# Airquality.net
KiCad netlist of a schematic drawn in EAGLE
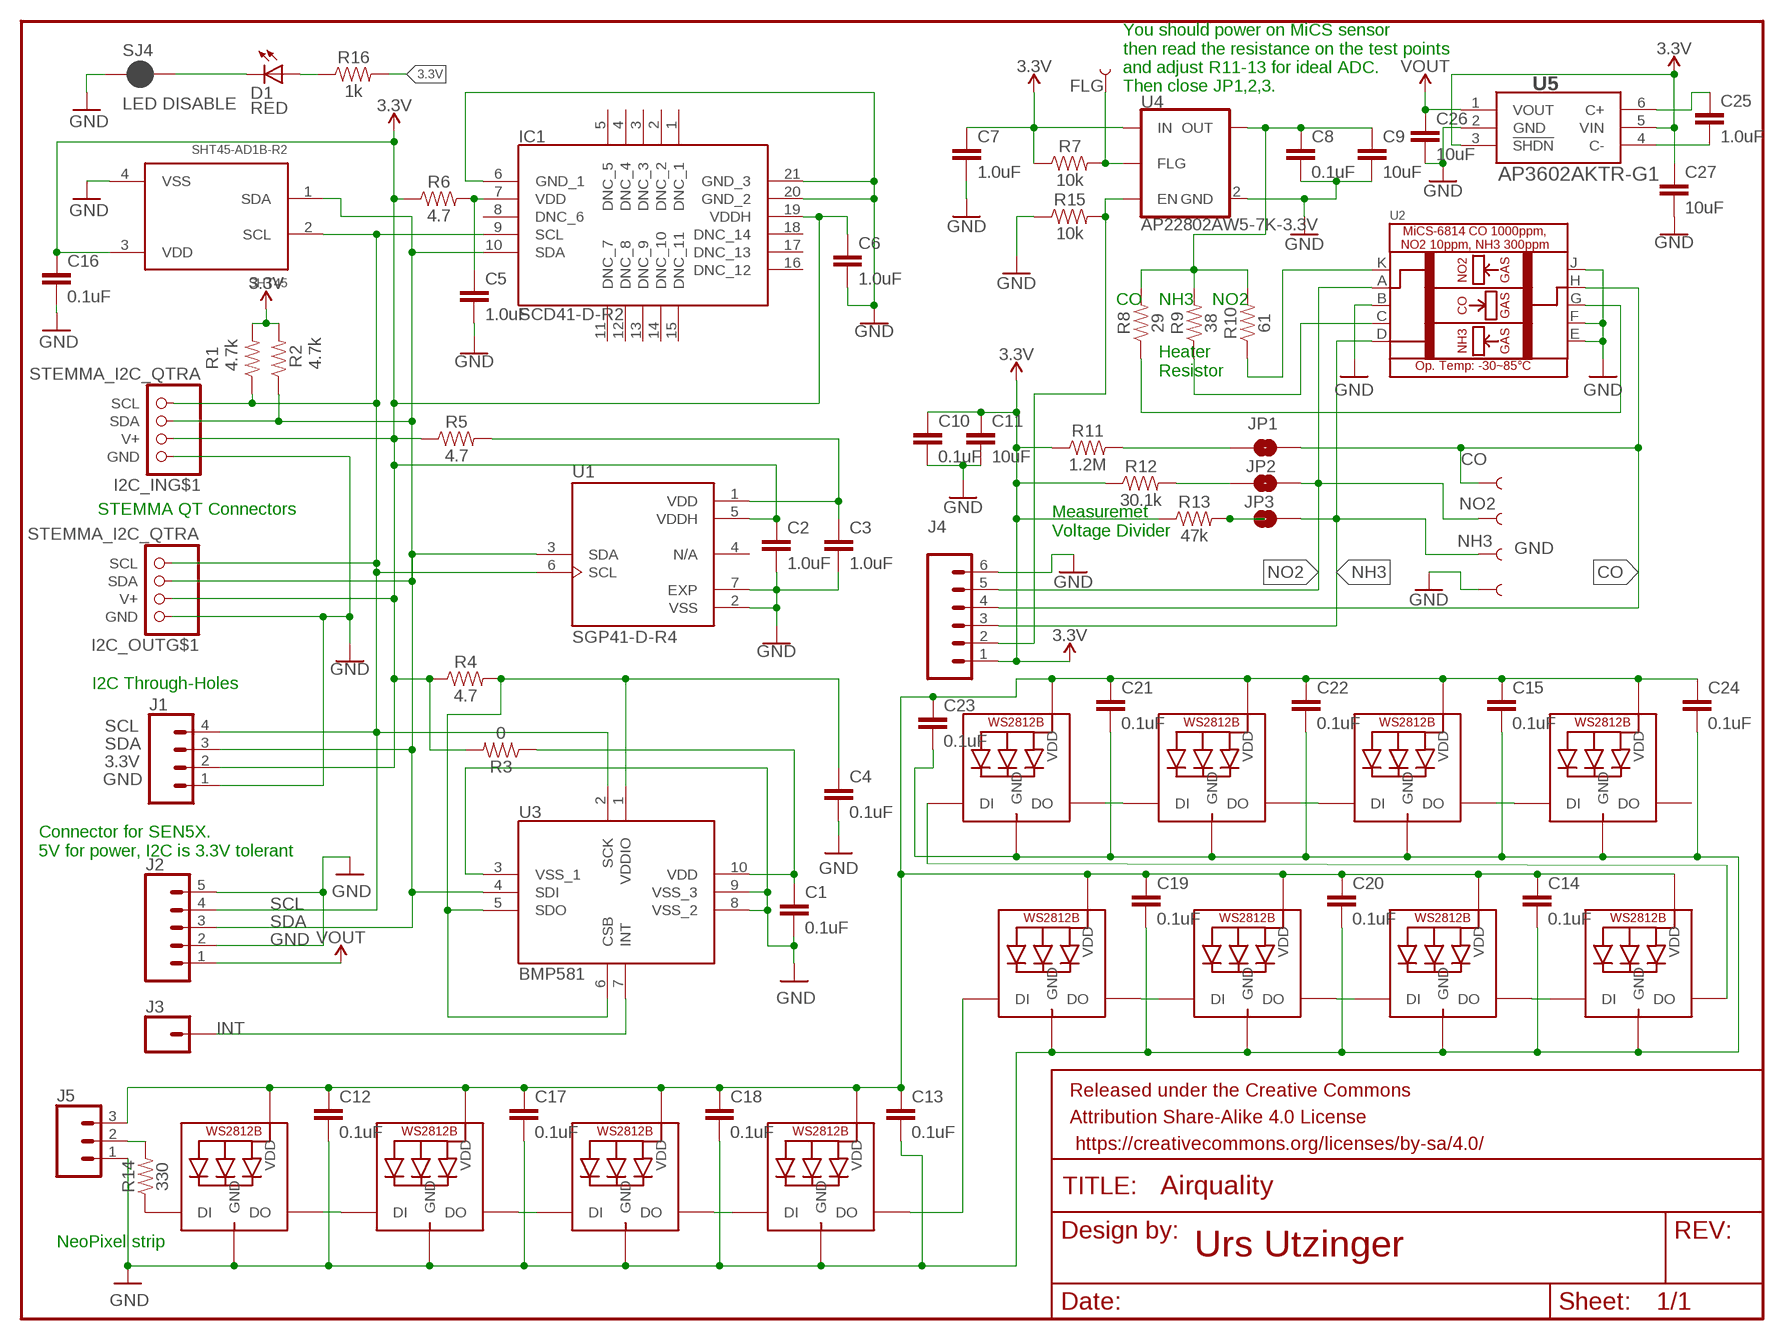
[diagram p0: schematic, sheet 1]

(export (version "E")
  (design (tool "Eeschema 10.0.6"))
  (components
    (comp (ref "C1")
      (value "0.1uF")
      (footprint "eagle-import:0603")
      (libsource (lib "eagle-import") (part "0.1UF-0603-25V-(+80/-20%)"))
    )
    (comp (ref "C2")
      (value "1.0uF")
      (footprint "eagle-import:0603")
      (libsource (lib "eagle-import") (part "1.0UF-0603-16V-10%"))
    )
    (comp (ref "C3")
      (value "1.0uF")
      (footprint "eagle-import:0603")
      (libsource (lib "eagle-import") (part "1.0UF-0603-16V-10%"))
    )
    (comp (ref "C4")
      (value "0.1uF")
      (footprint "eagle-import:0603")
      (libsource (lib "eagle-import") (part "0.1UF-0603-25V-(+80/-20%)"))
    )
    (comp (ref "C5")
      (value "1.0uF")
      (footprint "eagle-import:0603")
      (libsource (lib "eagle-import") (part "1.0UF-0603-16V-10%"))
    )
    (comp (ref "C6")
      (value "1.0uF")
      (footprint "eagle-import:0603")
      (libsource (lib "eagle-import") (part "1.0UF-0603-16V-10%"))
    )
    (comp (ref "C7")
      (value "1.0uF")
      (footprint "eagle-import:0603")
      (libsource (lib "eagle-import") (part "1.0UF-0603-16V-10%"))
    )
    (comp (ref "C8")
      (value "0.1uF")
      (footprint "eagle-import:0603")
      (libsource (lib "eagle-import") (part "0.1UF-0603-25V-(+80/-20%)"))
    )
    (comp (ref "C9")
      (value "10uF")
      (footprint "eagle-import:0603")
      (libsource (lib "eagle-import") (part "10UF-0603-6.3V-20%"))
    )
    (comp (ref "C10")
      (value "0.1uF")
      (footprint "eagle-import:0603")
      (libsource (lib "eagle-import") (part "0.1UF-0603-25V-(+80/-20%)"))
    )
    (comp (ref "C11")
      (value "10uF")
      (footprint "eagle-import:0603")
      (libsource (lib "eagle-import") (part "10UF-0603-6.3V-20%"))
    )
    (comp (ref "C12")
      (value "0.1uF")
      (footprint "eagle-import:0402")
      (libsource (lib "eagle-import") (part "0.1UF-0402-16V-10%"))
    )
    (comp (ref "C13")
      (value "0.1uF")
      (footprint "eagle-import:0402")
      (libsource (lib "eagle-import") (part "0.1UF-0402-16V-10%"))
    )
    (comp (ref "C14")
      (value "0.1uF")
      (footprint "eagle-import:0402")
      (libsource (lib "eagle-import") (part "0.1UF-0402-16V-10%"))
    )
    (comp (ref "C15")
      (value "0.1uF")
      (footprint "eagle-import:0402")
      (libsource (lib "eagle-import") (part "0.1UF-0402-16V-10%"))
    )
    (comp (ref "C16")
      (value "0.1uF")
      (footprint "eagle-import:0603")
      (libsource (lib "eagle-import") (part "0.1UF-0603-25V-(+80/-20%)"))
    )
    (comp (ref "C17")
      (value "0.1uF")
      (footprint "eagle-import:0402")
      (libsource (lib "eagle-import") (part "0.1UF-0402-16V-10%"))
    )
    (comp (ref "C18")
      (value "0.1uF")
      (footprint "eagle-import:0402")
      (libsource (lib "eagle-import") (part "0.1UF-0402-16V-10%"))
    )
    (comp (ref "C19")
      (value "0.1uF")
      (footprint "eagle-import:0402")
      (libsource (lib "eagle-import") (part "0.1UF-0402-16V-10%"))
    )
    (comp (ref "C20")
      (value "0.1uF")
      (footprint "eagle-import:0402")
      (libsource (lib "eagle-import") (part "0.1UF-0402-16V-10%"))
    )
    (comp (ref "C21")
      (value "0.1uF")
      (footprint "eagle-import:0402")
      (libsource (lib "eagle-import") (part "0.1UF-0402-16V-10%"))
    )
    (comp (ref "C22")
      (value "0.1uF")
      (footprint "eagle-import:0402")
      (libsource (lib "eagle-import") (part "0.1UF-0402-16V-10%"))
    )
    (comp (ref "C23")
      (value "0.1uF")
      (footprint "eagle-import:0402")
      (libsource (lib "eagle-import") (part "0.1UF-0402-16V-10%"))
    )
    (comp (ref "C24")
      (value "0.1uF")
      (footprint "eagle-import:0402")
      (libsource (lib "eagle-import") (part "0.1UF-0402-16V-10%"))
    )
    (comp (ref "C25")
      (value "1.0uF")
      (footprint "eagle-import:0402")
      (libsource (lib "eagle-import") (part "1.0UF-0402-16V-10%"))
    )
    (comp (ref "C26")
      (value "10uF")
      (footprint "eagle-import:0603")
      (libsource (lib "eagle-import") (part "10UF-0603-6.3V-20%"))
    )
    (comp (ref "C27")
      (value "10uF")
      (footprint "eagle-import:0603")
      (libsource (lib "eagle-import") (part "10UF-0603-6.3V-20%"))
    )
    (comp (ref "CO")
      (value "TEST-POINT3X4")
      (footprint "eagle-import:PAD.03X.04")
      (libsource (lib "eagle-import") (part "TEST-POINT3X4"))
    )
    (comp (ref "D1")
      (value "RED")
      (footprint "eagle-import:LED-0603")
      (libsource (lib "eagle-import") (part "LED-RED0603"))
    )
    (comp (ref "FLG")
      (value "TEST-POINT3X4")
      (footprint "eagle-import:PAD.03X.04")
      (libsource (lib "eagle-import") (part "TEST-POINT3X4"))
    )
    (comp (ref "FRAME1")
      (value "FRAME-LETTERNO_PACKAGE")
      (footprint "eagle-import:DUMMY")
      (fields (field (name "DESIGNER") "Nobody"))
      (libsource (lib "eagle-import") (part "FRAME-LETTERNO_PACKAGE"))
    )
    (comp (ref "GND")
      (value "TEST-POINT3X4")
      (footprint "eagle-import:PAD.03X.04")
      (libsource (lib "eagle-import") (part "TEST-POINT3X4"))
    )
    (comp (ref "I2C_IN")
      (value "STEMMA_I2C_QTRA")
      (footprint "eagle-import:JST_SH4_RA")
      (libsource (lib "eagle-import") (part "STEMMA_I2C_QTRA"))
    )
    (comp (ref "I2C_OUT")
      (value "STEMMA_I2C_QTRA")
      (footprint "eagle-import:JST_SH4_RA")
      (libsource (lib "eagle-import") (part "STEMMA_I2C_QTRA"))
    )
    (comp (ref "IC1")
      (value "SCD41-D-R2")
      (footprint "eagle-import:SCD41DR2")
      (fields (field (name "MOUSER_PART_NUMBER") "403-SCD41-D-R2"))
      (libsource (lib "eagle-import") (part "SCD41-D-R2"))
    )
    (comp (ref "J1")
      (value "CONN_04")
      (footprint "eagle-import:1X04")
      (libsource (lib "eagle-import") (part "CONN_04"))
    )
    (comp (ref "J2")
      (value "CONN_05")
      (footprint "eagle-import:1X05")
      (libsource (lib "eagle-import") (part "CONN_05"))
    )
    (comp (ref "J3")
      (value "CONN_01")
      (footprint "eagle-import:1X01")
      (libsource (lib "eagle-import") (part "CONN_01"))
    )
    (comp (ref "J4")
      (value "CONN_06SILK_FEMALE_PTH")
      (footprint "eagle-import:1X06")
      (libsource (lib "eagle-import") (part "CONN_06SILK_FEMALE_PTH"))
    )
    (comp (ref "J5")
      (value "CONN_03")
      (footprint "eagle-import:1X03")
      (libsource (lib "eagle-import") (part "CONN_03"))
    )
    (comp (ref "JP1")
      (value "JUMPER-SMT_2_NO_SILK")
      (footprint "eagle-import:SMT-JUMPER_2_NO_SILK")
      (libsource (lib "eagle-import") (part "JUMPER-SMT_2_NO_SILK"))
    )
    (comp (ref "JP2")
      (value "JUMPER-SMT_2_NO_SILK")
      (footprint "eagle-import:SMT-JUMPER_2_NO_SILK")
      (libsource (lib "eagle-import") (part "JUMPER-SMT_2_NO_SILK"))
    )
    (comp (ref "JP3")
      (value "JUMPER-SMT_2_NO_SILK")
      (footprint "eagle-import:SMT-JUMPER_2_NO_SILK")
      (libsource (lib "eagle-import") (part "JUMPER-SMT_2_NO_SILK"))
    )
    (comp (ref "LED0")
      (value "WS2812B_2020")
      (footprint "eagle-import:WS2812B_2020")
      (libsource (lib "eagle-import") (part "WS2812B_2020"))
    )
    (comp (ref "LED1")
      (value "WS2812B_2020")
      (footprint "eagle-import:WS2812B_2020")
      (libsource (lib "eagle-import") (part "WS2812B_2020"))
    )
    (comp (ref "LED2")
      (value "WS2812B_2020")
      (footprint "eagle-import:WS2812B_2020")
      (libsource (lib "eagle-import") (part "WS2812B_2020"))
    )
    (comp (ref "LED3")
      (value "WS2812B_2020")
      (footprint "eagle-import:WS2812B_2020")
      (libsource (lib "eagle-import") (part "WS2812B_2020"))
    )
    (comp (ref "LED4")
      (value "WS2812B_2020")
      (footprint "eagle-import:WS2812B_2020")
      (libsource (lib "eagle-import") (part "WS2812B_2020"))
    )
    (comp (ref "LED5")
      (value "WS2812B_2020")
      (footprint "eagle-import:WS2812B_2020")
      (libsource (lib "eagle-import") (part "WS2812B_2020"))
    )
    (comp (ref "LED6")
      (value "WS2812B_2020")
      (footprint "eagle-import:WS2812B_2020")
      (libsource (lib "eagle-import") (part "WS2812B_2020"))
    )
    (comp (ref "LED7")
      (value "WS2812B_2020")
      (footprint "eagle-import:WS2812B_2020")
      (libsource (lib "eagle-import") (part "WS2812B_2020"))
    )
    (comp (ref "LED8")
      (value "WS2812B_2020")
      (footprint "eagle-import:WS2812B_2020")
      (libsource (lib "eagle-import") (part "WS2812B_2020"))
    )
    (comp (ref "LED9")
      (value "WS2812B_2020")
      (footprint "eagle-import:WS2812B_2020")
      (libsource (lib "eagle-import") (part "WS2812B_2020"))
    )
    (comp (ref "LED10")
      (value "WS2812B_2020")
      (footprint "eagle-import:WS2812B_2020")
      (libsource (lib "eagle-import") (part "WS2812B_2020"))
    )
    (comp (ref "LED11")
      (value "WS2812B_2020")
      (footprint "eagle-import:WS2812B_2020")
      (libsource (lib "eagle-import") (part "WS2812B_2020"))
    )
    (comp (ref "NH3")
      (value "TEST-POINT3X4")
      (footprint "eagle-import:PAD.03X.04")
      (libsource (lib "eagle-import") (part "TEST-POINT3X4"))
    )
    (comp (ref "NO2")
      (value "TEST-POINT3X4")
      (footprint "eagle-import:PAD.03X.04")
      (libsource (lib "eagle-import") (part "TEST-POINT3X4"))
    )
    (comp (ref "R1")
      (value "4.7k")
      (footprint "eagle-import:0603")
      (libsource (lib "eagle-import") (part "4.7KOHM-0603-1/10W-1%"))
    )
    (comp (ref "R2")
      (value "4.7k")
      (footprint "eagle-import:0603")
      (libsource (lib "eagle-import") (part "4.7KOHM-0603-1/10W-1%"))
    )
    (comp (ref "R3")
      (value "0")
      (footprint "eagle-import:0603")
      (libsource (lib "eagle-import") (part "10OHM-0603-1/10W-5%"))
    )
    (comp (ref "R4")
      (value "4.7")
      (footprint "eagle-import:0603")
      (libsource (lib "eagle-import") (part "10OHM-0603-1/10W-5%"))
    )
    (comp (ref "R5")
      (value "4.7")
      (footprint "eagle-import:0603")
      (libsource (lib "eagle-import") (part "10OHM-0603-1/10W-1%"))
    )
    (comp (ref "R6")
      (value "4.7")
      (footprint "eagle-import:0603")
      (libsource (lib "eagle-import") (part "10OHM-0603-1/10W-1%"))
    )
    (comp (ref "R7")
      (value "10k")
      (footprint "eagle-import:0603")
      (libsource (lib "eagle-import") (part "10KOHM-0603-1/10W-1%"))
    )
    (comp (ref "R8")
      (value "29")
      (footprint "eagle-import:0603")
      (libsource (lib "eagle-import") (part "27OHM-0603-1/10W-1%"))
    )
    (comp (ref "R9")
      (value "38")
      (footprint "eagle-import:0603")
      (libsource (lib "eagle-import") (part "33OHM-0603-1/10W-1%"))
    )
    (comp (ref "R10")
      (value "61")
      (footprint "eagle-import:0603")
      (libsource (lib "eagle-import") (part "82OHM-0603-1/10W-1%"))
    )
    (comp (ref "R11")
      (value "1.2M")
      (footprint "eagle-import:0603")
      (libsource (lib "eagle-import") (part "1.2MOHM-0603-1/10W-1%"))
    )
    (comp (ref "R12")
      (value "30.1k")
      (footprint "eagle-import:0603")
      (libsource (lib "eagle-import") (part "30.1KOHM-0603-1/10W-1%"))
    )
    (comp (ref "R13")
      (value "47k")
      (footprint "eagle-import:0603")
      (libsource (lib "eagle-import") (part "47KOHM-0603-1/10W-1%"))
    )
    (comp (ref "R14")
      (value "330")
      (footprint "eagle-import:0603")
      (libsource (lib "eagle-import") (part "330OHM-0603-1/10W-1%"))
    )
    (comp (ref "R15")
      (value "10k")
      (footprint "eagle-import:0603")
      (libsource (lib "eagle-import") (part "10KOHM-0603-1/10W-1%"))
    )
    (comp (ref "R16")
      (value "1k")
      (footprint "eagle-import:0603")
      (libsource (lib "eagle-import") (part "1KOHM-0603-1/10W-1%"))
    )
    (comp (ref "SHT45")
      (value "SHT45-AD1B-R2")
      (footprint "eagle-import:SHT4X")
      (libsource (lib "eagle-import") (part "SHT45-AD1B-R2"))
    )
    (comp (ref "SJ4")
      (value "LED DISABLE")
      (footprint "eagle-import:SMT-JUMPER_2_NC_PASTE_SILK")
      (libsource (lib "eagle-import") (part "JUMPER-SMT_2_NC_PASTE_SILK"))
    )
    (comp (ref "U1")
      (value "SGP41-D-R4")
      (footprint "eagle-import:XDCR_SGP41-D-R4")
      (fields (field (name "MANUFACTURER") "Sensirion"))
      (libsource (lib "eagle-import") (part "SGP41-D-R4"))
    )
    (comp (ref "U2")
      (value "MICROBUILDER_MICS-5524")
      (footprint "eagle-import:MICROBUILDER_MICS-5524")
      (libsource (lib "eagle-import") (part "MICROBUILDER_MICS-5524"))
    )
    (comp (ref "U3")
      (value "BMP581")
      (footprint "eagle-import:BMP581")
      (fields (field (name "MOUSER_PART_NUMBER") "262-BMP581"))
      (libsource (lib "eagle-import") (part "BMP581"))
    )
    (comp (ref "U4")
      (value "AP22802AW5-7K-3.3V")
      (footprint "eagle-import:SOT25")
      (libsource (lib "eagle-import") (part "AP22802AW5-7K-3.3V"))
    )
    (comp (ref "U5")
      (value "AP3602AKTR-G1")
      (footprint "eagle-import:SOT95P280X125-6N")
      (fields (field (name "MOUSER_PART_NUMBER") "621-AP3602AKTR-G1"))
      (libsource (lib "eagle-import") (part "AP3602AKTR-G1"))
    )
  )
  (nets
    (net (code "1") (name "/INT") (class "Default")
      (node (ref "J3") (pin "1") (pinfunction "1_1") (pintype "passive"))
      (node (ref "U3") (pin "7") (pinfunction "INT_7") (pintype "bidirectional"))
    )
    (net (code "2") (name "/SCL") (class "Default")
      (node (ref "I2C_IN") (pin "4") (pinfunction "SCL_4") (pintype "passive"))
      (node (ref "I2C_OUT") (pin "4") (pinfunction "SCL_4") (pintype "passive"))
      (node (ref "IC1") (pin "9") (pinfunction "SCL_9") (pintype "bidirectional"))
      (node (ref "J1") (pin "4") (pinfunction "4_4") (pintype "passive"))
      (node (ref "J2") (pin "4") (pinfunction "4_4") (pintype "passive"))
      (node (ref "R1") (pin "1") (pinfunction "1_1") (pintype "passive"))
      (node (ref "SHT45") (pin "2") (pinfunction "SCL_2") (pintype "input"))
      (node (ref "U1") (pin "6") (pinfunction "SCL_6") (pintype "bidirectional"))
      (node (ref "U3") (pin "2") (pinfunction "SCK_2") (pintype "bidirectional"))
    )
    (net (code "3") (name "/SDA") (class "Default")
      (node (ref "I2C_IN") (pin "3") (pinfunction "SDA_3") (pintype "passive"))
      (node (ref "I2C_OUT") (pin "3") (pinfunction "SDA_3") (pintype "passive"))
      (node (ref "IC1") (pin "10") (pinfunction "SDA_10") (pintype "bidirectional"))
      (node (ref "J1") (pin "3") (pinfunction "3_3") (pintype "passive"))
      (node (ref "J2") (pin "3") (pinfunction "3_3") (pintype "passive"))
      (node (ref "R2") (pin "1") (pinfunction "1_1") (pintype "passive"))
      (node (ref "SHT45") (pin "1") (pinfunction "SDA_1") (pintype "bidirectional"))
      (node (ref "U1") (pin "3") (pinfunction "SDA_3") (pintype "bidirectional"))
      (node (ref "U3") (pin "4") (pinfunction "SDI_4") (pintype "bidirectional"))
    )
    (net (code "4") (name "3.3V") (class "Default")
      (node (ref "C10") (pin "1") (pinfunction "1_1") (pintype "passive"))
      (node (ref "C11") (pin "1") (pinfunction "1_1") (pintype "passive"))
      (node (ref "C16") (pin "1") (pinfunction "1_1") (pintype "passive"))
      (node (ref "C2") (pin "1") (pinfunction "1_1") (pintype "passive"))
      (node (ref "C27") (pin "1") (pinfunction "1_1") (pintype "passive"))
      (node (ref "C6") (pin "1") (pinfunction "1_1") (pintype "passive"))
      (node (ref "C7") (pin "1") (pinfunction "1_1") (pintype "passive"))
      (node (ref "I2C_IN") (pin "2") (pinfunction "V+_2") (pintype "passive"))
      (node (ref "I2C_OUT") (pin "2") (pinfunction "V+_2") (pintype "passive"))
      (node (ref "IC1") (pin "19") (pinfunction "VDDH_19") (pintype "bidirectional"))
      (node (ref "J1") (pin "2") (pinfunction "2_2") (pintype "passive"))
      (node (ref "J4") (pin "1") (pinfunction "1_1") (pintype "passive"))
      (node (ref "R1") (pin "2") (pinfunction "2_2") (pintype "passive"))
      (node (ref "R11") (pin "1") (pinfunction "1_1") (pintype "passive"))
      (node (ref "R12") (pin "1") (pinfunction "1_1") (pintype "passive"))
      (node (ref "R13") (pin "1") (pinfunction "1_1") (pintype "passive"))
      (node (ref "R16") (pin "2") (pinfunction "2_2") (pintype "passive"))
      (node (ref "R2") (pin "2") (pinfunction "2_2") (pintype "passive"))
      (node (ref "R3") (pin "2") (pinfunction "2_2") (pintype "passive"))
      (node (ref "R4") (pin "1") (pinfunction "1_1") (pintype "passive"))
      (node (ref "R5") (pin "1") (pinfunction "1_1") (pintype "passive"))
      (node (ref "R6") (pin "1") (pinfunction "1_1") (pintype "passive"))
      (node (ref "R7") (pin "1") (pinfunction "1_1") (pintype "passive"))
      (node (ref "SHT45") (pin "3") (pinfunction "VDD_3") (pintype "power_in"))
      (node (ref "U1") (pin "5") (pinfunction "VDDH_5") (pintype "power_in"))
      (node (ref "U4") (pin "5") (pinfunction "IN_5") (pintype "input"))
      (node (ref "U5") (pin "3") (pinfunction "~{SHDN}_3") (pintype "bidirectional"))
      (node (ref "U5") (pin "5") (pinfunction "VIN_5") (pintype "bidirectional"))
    )
    (net (code "5") (name "CO") (class "Default")
      (node (ref "CO") (pin "P$1") (pinfunction "1_P$1") (pintype "bidirectional"))
      (node (ref "J4") (pin "4") (pinfunction "4_4") (pintype "passive"))
      (node (ref "JP1") (pin "2") (pinfunction "2_2") (pintype "passive"))
      (node (ref "U2") (pin "H") (pinfunction "H_H") (pintype "bidirectional"))
    )
    (net (code "6") (name "GND") (class "Default")
      (node (ref "C1") (pin "2") (pinfunction "2_2") (pintype "passive"))
      (node (ref "C10") (pin "2") (pinfunction "2_2") (pintype "passive"))
      (node (ref "C11") (pin "2") (pinfunction "2_2") (pintype "passive"))
      (node (ref "C12") (pin "2") (pinfunction "2_2") (pintype "passive"))
      (node (ref "C13") (pin "2") (pinfunction "2_2") (pintype "passive"))
      (node (ref "C14") (pin "2") (pinfunction "2_2") (pintype "passive"))
      (node (ref "C15") (pin "2") (pinfunction "2_2") (pintype "passive"))
      (node (ref "C16") (pin "2") (pinfunction "2_2") (pintype "passive"))
      (node (ref "C17") (pin "2") (pinfunction "2_2") (pintype "passive"))
      (node (ref "C18") (pin "2") (pinfunction "2_2") (pintype "passive"))
      (node (ref "C19") (pin "2") (pinfunction "2_2") (pintype "passive"))
      (node (ref "C2") (pin "2") (pinfunction "2_2") (pintype "passive"))
      (node (ref "C20") (pin "2") (pinfunction "2_2") (pintype "passive"))
      (node (ref "C21") (pin "2") (pinfunction "2_2") (pintype "passive"))
      (node (ref "C22") (pin "2") (pinfunction "2_2") (pintype "passive"))
      (node (ref "C23") (pin "2") (pinfunction "2_2") (pintype "passive"))
      (node (ref "C24") (pin "2") (pinfunction "2_2") (pintype "passive"))
      (node (ref "C26") (pin "2") (pinfunction "2_2") (pintype "passive"))
      (node (ref "C27") (pin "2") (pinfunction "2_2") (pintype "passive"))
      (node (ref "C3") (pin "2") (pinfunction "2_2") (pintype "passive"))
      (node (ref "C4") (pin "2") (pinfunction "2_2") (pintype "passive"))
      (node (ref "C5") (pin "2") (pinfunction "2_2") (pintype "passive"))
      (node (ref "C6") (pin "2") (pinfunction "2_2") (pintype "passive"))
      (node (ref "C7") (pin "2") (pinfunction "2_2") (pintype "passive"))
      (node (ref "C8") (pin "2") (pinfunction "2_2") (pintype "passive"))
      (node (ref "C9") (pin "2") (pinfunction "2_2") (pintype "passive"))
      (node (ref "GND") (pin "P$1") (pinfunction "1_P$1") (pintype "bidirectional"))
      (node (ref "I2C_IN") (pin "1") (pinfunction "GND_1") (pintype "passive"))
      (node (ref "I2C_OUT") (pin "1") (pinfunction "GND_1") (pintype "passive"))
      (node (ref "IC1") (pin "20") (pinfunction "GND_2_20") (pintype "bidirectional"))
      (node (ref "IC1") (pin "21") (pinfunction "GND_3_21") (pintype "bidirectional"))
      (node (ref "IC1") (pin "6") (pinfunction "GND_1_6") (pintype "bidirectional"))
      (node (ref "J1") (pin "1") (pinfunction "1_1") (pintype "passive"))
      (node (ref "J2") (pin "2") (pinfunction "2_2") (pintype "passive"))
      (node (ref "J2") (pin "5") (pinfunction "5_5") (pintype "passive"))
      (node (ref "J4") (pin "6") (pinfunction "6_6") (pintype "passive"))
      (node (ref "J5") (pin "1") (pinfunction "1_1") (pintype "passive"))
      (node (ref "LED0") (pin "2") (pinfunction "GND_2") (pintype "power_in"))
      (node (ref "LED1") (pin "2") (pinfunction "GND_2") (pintype "power_in"))
      (node (ref "LED10") (pin "2") (pinfunction "GND_2") (pintype "power_in"))
      (node (ref "LED11") (pin "2") (pinfunction "GND_2") (pintype "power_in"))
      (node (ref "LED2") (pin "2") (pinfunction "GND_2") (pintype "power_in"))
      (node (ref "LED3") (pin "2") (pinfunction "GND_2") (pintype "power_in"))
      (node (ref "LED4") (pin "2") (pinfunction "GND_2") (pintype "power_in"))
      (node (ref "LED5") (pin "2") (pinfunction "GND_2") (pintype "power_in"))
      (node (ref "LED6") (pin "2") (pinfunction "GND_2") (pintype "power_in"))
      (node (ref "LED7") (pin "2") (pinfunction "GND_2") (pintype "power_in"))
      (node (ref "LED8") (pin "2") (pinfunction "GND_2") (pintype "power_in"))
      (node (ref "LED9") (pin "2") (pinfunction "GND_2") (pintype "power_in"))
      (node (ref "R15") (pin "1") (pinfunction "1_1") (pintype "passive"))
      (node (ref "SHT45") (pin "4") (pinfunction "VSS_4") (pintype "power_in"))
      (node (ref "SJ4") (pin "1") (pinfunction "1_1") (pintype "passive"))
      (node (ref "U1") (pin "2") (pinfunction "VSS_2") (pintype "power_in"))
      (node (ref "U1") (pin "7") (pinfunction "EXP_7") (pintype "power_in"))
      (node (ref "U2") (pin "B") (pinfunction "B_B") (pintype "bidirectional"))
      (node (ref "U2") (pin "E") (pinfunction "E_E") (pintype "bidirectional"))
      (node (ref "U2") (pin "F") (pinfunction "F_F") (pintype "bidirectional"))
      (node (ref "U2") (pin "J") (pinfunction "J_J") (pintype "bidirectional"))
      (node (ref "U3") (pin "3") (pinfunction "VSS_1_3") (pintype "bidirectional"))
      (node (ref "U3") (pin "8") (pinfunction "VSS_2_8") (pintype "bidirectional"))
      (node (ref "U3") (pin "9") (pinfunction "VSS_3_9") (pintype "bidirectional"))
      (node (ref "U4") (pin "2") (pinfunction "GND_2") (pintype "input"))
      (node (ref "U5") (pin "2") (pinfunction "GND_2") (pintype "bidirectional"))
    )
    (net (code "7") (name "NH3") (class "Default")
      (node (ref "J4") (pin "3") (pinfunction "3_3") (pintype "passive"))
      (node (ref "JP3") (pin "2") (pinfunction "2_2") (pintype "passive"))
      (node (ref "NH3") (pin "P$1") (pinfunction "1_P$1") (pintype "bidirectional"))
      (node (ref "U2") (pin "D") (pinfunction "D_D") (pintype "bidirectional"))
    )
    (net (code "8") (name "NO2") (class "Default")
      (node (ref "J4") (pin "5") (pinfunction "5_5") (pintype "passive"))
      (node (ref "JP2") (pin "2") (pinfunction "2_2") (pintype "passive"))
      (node (ref "NO2") (pin "P$1") (pinfunction "1_P$1") (pintype "bidirectional"))
      (node (ref "U2") (pin "A") (pinfunction "A_A") (pintype "bidirectional"))
    )
    (net (code "9") (name "Net-(D1-PadA)") (class "Default")
      (node (ref "D1") (pin "A") (pinfunction "A_A") (pintype "passive"))
      (node (ref "R16") (pin "1") (pinfunction "1_1") (pintype "passive"))
    )
    (net (code "10") (name "Net-(D1-PadC)") (class "Default")
      (node (ref "D1") (pin "C") (pinfunction "C_C") (pintype "passive"))
      (node (ref "SJ4") (pin "2") (pinfunction "2_2") (pintype "passive"))
    )
    (net (code "11") (name "Net-(FLG-1)") (class "Default")
      (node (ref "FLG") (pin "P$1") (pinfunction "1_P$1") (pintype "bidirectional"))
      (node (ref "R7") (pin "2") (pinfunction "2_2") (pintype "passive"))
      (node (ref "U4") (pin "3") (pinfunction "FLG_3") (pintype "input"))
    )
    (net (code "12") (name "Net-(IC1-VDD)") (class "Default")
      (node (ref "C5") (pin "1") (pinfunction "1_1") (pintype "passive"))
      (node (ref "IC1") (pin "7") (pinfunction "VDD_7") (pintype "bidirectional"))
      (node (ref "R6") (pin "2") (pinfunction "2_2") (pintype "passive"))
    )
    (net (code "13") (name "Net-(J5-Pad2)") (class "Default")
      (node (ref "J5") (pin "2") (pinfunction "2_2") (pintype "passive"))
      (node (ref "R14") (pin "2") (pinfunction "2_2") (pintype "passive"))
    )
    (net (code "14") (name "Net-(JP1-Pad1)") (class "Default")
      (node (ref "JP1") (pin "1") (pinfunction "1_1") (pintype "passive"))
      (node (ref "R11") (pin "2") (pinfunction "2_2") (pintype "passive"))
    )
    (net (code "15") (name "Net-(JP2-Pad1)") (class "Default")
      (node (ref "JP2") (pin "1") (pinfunction "1_1") (pintype "passive"))
      (node (ref "R12") (pin "2") (pinfunction "2_2") (pintype "passive"))
    )
    (net (code "16") (name "Net-(JP3-Pad1)") (class "Default")
      (node (ref "JP3") (pin "1") (pinfunction "1_1") (pintype "passive"))
      (node (ref "R13") (pin "2") (pinfunction "2_2") (pintype "passive"))
    )
    (net (code "17") (name "Net-(LED0-DI)") (class "Default")
      (node (ref "LED0") (pin "3") (pinfunction "DI_3") (pintype "input"))
      (node (ref "R14") (pin "1") (pinfunction "1_1") (pintype "passive"))
    )
    (net (code "18") (name "Net-(LED0-DO)") (class "Default")
      (node (ref "LED0") (pin "1") (pinfunction "DO_1") (pintype "output"))
      (node (ref "LED1") (pin "3") (pinfunction "DI_3") (pintype "input"))
    )
    (net (code "19") (name "Net-(LED0-VDD)") (class "Default")
      (node (ref "C12") (pin "1") (pinfunction "1_1") (pintype "passive"))
      (node (ref "C13") (pin "1") (pinfunction "1_1") (pintype "passive"))
      (node (ref "C14") (pin "1") (pinfunction "1_1") (pintype "passive"))
      (node (ref "C15") (pin "1") (pinfunction "1_1") (pintype "passive"))
      (node (ref "C17") (pin "1") (pinfunction "1_1") (pintype "passive"))
      (node (ref "C18") (pin "1") (pinfunction "1_1") (pintype "passive"))
      (node (ref "C19") (pin "1") (pinfunction "1_1") (pintype "passive"))
      (node (ref "C20") (pin "1") (pinfunction "1_1") (pintype "passive"))
      (node (ref "C21") (pin "1") (pinfunction "1_1") (pintype "passive"))
      (node (ref "C22") (pin "1") (pinfunction "1_1") (pintype "passive"))
      (node (ref "C23") (pin "1") (pinfunction "1_1") (pintype "passive"))
      (node (ref "C24") (pin "1") (pinfunction "1_1") (pintype "passive"))
      (node (ref "J5") (pin "3") (pinfunction "3_3") (pintype "passive"))
      (node (ref "LED0") (pin "4") (pinfunction "VDD_4") (pintype "power_in"))
      (node (ref "LED1") (pin "4") (pinfunction "VDD_4") (pintype "power_in"))
      (node (ref "LED10") (pin "4") (pinfunction "VDD_4") (pintype "power_in"))
      (node (ref "LED11") (pin "4") (pinfunction "VDD_4") (pintype "power_in"))
      (node (ref "LED2") (pin "4") (pinfunction "VDD_4") (pintype "power_in"))
      (node (ref "LED3") (pin "4") (pinfunction "VDD_4") (pintype "power_in"))
      (node (ref "LED4") (pin "4") (pinfunction "VDD_4") (pintype "power_in"))
      (node (ref "LED5") (pin "4") (pinfunction "VDD_4") (pintype "power_in"))
      (node (ref "LED6") (pin "4") (pinfunction "VDD_4") (pintype "power_in"))
      (node (ref "LED7") (pin "4") (pinfunction "VDD_4") (pintype "power_in"))
      (node (ref "LED8") (pin "4") (pinfunction "VDD_4") (pintype "power_in"))
      (node (ref "LED9") (pin "4") (pinfunction "VDD_4") (pintype "power_in"))
    )
    (net (code "20") (name "Net-(LED1-DO)") (class "Default")
      (node (ref "LED1") (pin "1") (pinfunction "DO_1") (pintype "output"))
      (node (ref "LED2") (pin "3") (pinfunction "DI_3") (pintype "input"))
    )
    (net (code "21") (name "Net-(LED2-DO)") (class "Default")
      (node (ref "LED2") (pin "1") (pinfunction "DO_1") (pintype "output"))
      (node (ref "LED3") (pin "3") (pinfunction "DI_3") (pintype "input"))
    )
    (net (code "22") (name "Net-(LED3-DO)") (class "Default")
      (node (ref "LED3") (pin "1") (pinfunction "DO_1") (pintype "output"))
      (node (ref "LED4") (pin "3") (pinfunction "DI_3") (pintype "input"))
    )
    (net (code "23") (name "Net-(LED4-DO)") (class "Default")
      (node (ref "LED4") (pin "1") (pinfunction "DO_1") (pintype "output"))
      (node (ref "LED5") (pin "3") (pinfunction "DI_3") (pintype "input"))
    )
    (net (code "24") (name "Net-(LED5-DO)") (class "Default")
      (node (ref "LED5") (pin "1") (pinfunction "DO_1") (pintype "output"))
      (node (ref "LED6") (pin "3") (pinfunction "DI_3") (pintype "input"))
    )
    (net (code "25") (name "Net-(LED6-DO)") (class "Default")
      (node (ref "LED6") (pin "1") (pinfunction "DO_1") (pintype "output"))
      (node (ref "LED7") (pin "3") (pinfunction "DI_3") (pintype "input"))
    )
    (net (code "26") (name "Net-(LED7-DO)") (class "Default")
      (node (ref "LED7") (pin "1") (pinfunction "DO_1") (pintype "output"))
      (node (ref "LED8") (pin "3") (pinfunction "DI_3") (pintype "input"))
    )
    (net (code "27") (name "Net-(LED8-DO)") (class "Default")
      (node (ref "LED8") (pin "1") (pinfunction "DO_1") (pintype "output"))
      (node (ref "LED9") (pin "3") (pinfunction "DI_3") (pintype "input"))
    )
    (net (code "28") (name "Net-(LED10-DI)") (class "Default")
      (node (ref "LED10") (pin "3") (pinfunction "DI_3") (pintype "input"))
      (node (ref "LED9") (pin "1") (pinfunction "DO_1") (pintype "output"))
    )
    (net (code "29") (name "Net-(LED10-DO)") (class "Default")
      (node (ref "LED10") (pin "1") (pinfunction "DO_1") (pintype "output"))
      (node (ref "LED11") (pin "3") (pinfunction "DI_3") (pintype "input"))
    )
    (net (code "30") (name "Net-(R8-Pad1)") (class "Default")
      (node (ref "R8") (pin "1") (pinfunction "1_1") (pintype "passive"))
      (node (ref "U2") (pin "G") (pinfunction "G_G") (pintype "bidirectional"))
    )
    (net (code "31") (name "Net-(R9-Pad1)") (class "Default")
      (node (ref "R9") (pin "1") (pinfunction "1_1") (pintype "passive"))
      (node (ref "U2") (pin "C") (pinfunction "C_C") (pintype "bidirectional"))
    )
    (net (code "32") (name "Net-(R10-Pad1)") (class "Default")
      (node (ref "R10") (pin "1") (pinfunction "1_1") (pintype "passive"))
      (node (ref "U2") (pin "K") (pinfunction "K_K") (pintype "bidirectional"))
    )
    (net (code "33") (name "Net-(U1-VDD)") (class "Default")
      (node (ref "C3") (pin "1") (pinfunction "1_1") (pintype "passive"))
      (node (ref "R5") (pin "2") (pinfunction "2_2") (pintype "passive"))
      (node (ref "U1") (pin "1") (pinfunction "VDD_1") (pintype "power_in"))
    )
    (net (code "34") (name "Net-(U3-CSB)") (class "Default")
      (node (ref "C4") (pin "1") (pinfunction "1_1") (pintype "passive"))
      (node (ref "R4") (pin "2") (pinfunction "2_2") (pintype "passive"))
      (node (ref "U3") (pin "1") (pinfunction "VDDIO_1") (pintype "bidirectional"))
      (node (ref "U3") (pin "5") (pinfunction "SDO_5") (pintype "bidirectional"))
      (node (ref "U3") (pin "6") (pinfunction "CSB_6") (pintype "bidirectional"))
    )
    (net (code "35") (name "Net-(U3-VDD)") (class "Default")
      (node (ref "C1") (pin "1") (pinfunction "1_1") (pintype "passive"))
      (node (ref "R3") (pin "1") (pinfunction "1_1") (pintype "passive"))
      (node (ref "U3") (pin "10") (pinfunction "VDD_10") (pintype "bidirectional"))
    )
    (net (code "36") (name "Net-(U4-EN)") (class "Default")
      (node (ref "J4") (pin "2") (pinfunction "2_2") (pintype "passive"))
      (node (ref "R15") (pin "2") (pinfunction "2_2") (pintype "passive"))
      (node (ref "U4") (pin "4") (pinfunction "EN_4") (pintype "input"))
    )
    (net (code "37") (name "Net-(U4-OUT)") (class "Default")
      (node (ref "C8") (pin "1") (pinfunction "1_1") (pintype "passive"))
      (node (ref "C9") (pin "1") (pinfunction "1_1") (pintype "passive"))
      (node (ref "R10") (pin "2") (pinfunction "2_2") (pintype "passive"))
      (node (ref "R8") (pin "2") (pinfunction "2_2") (pintype "passive"))
      (node (ref "R9") (pin "2") (pinfunction "2_2") (pintype "passive"))
      (node (ref "U4") (pin "1") (pinfunction "OUT_1") (pintype "passive"))
    )
    (net (code "38") (name "Net-(U5-C+)") (class "Default")
      (node (ref "C25") (pin "1") (pinfunction "1_1") (pintype "passive"))
      (node (ref "U5") (pin "6") (pinfunction "C+_6") (pintype "bidirectional"))
    )
    (net (code "39") (name "Net-(U5-C-)") (class "Default")
      (node (ref "C25") (pin "2") (pinfunction "2_2") (pintype "passive"))
      (node (ref "U5") (pin "4") (pinfunction "C-_4") (pintype "bidirectional"))
    )
    (net (code "40") (name "VOUT") (class "Default")
      (node (ref "C26") (pin "1") (pinfunction "1_1") (pintype "passive"))
      (node (ref "J2") (pin "1") (pinfunction "1_1") (pintype "passive"))
      (node (ref "U5") (pin "1") (pinfunction "VOUT_1") (pintype "bidirectional"))
    )
    (net (code "41") (name "unconnected-(IC1-DNC_1-Pad1)") (class "Default")
      (node (ref "IC1") (pin "1") (pinfunction "DNC_1_1") (pintype "bidirectional"))
    )
    (net (code "42") (name "unconnected-(IC1-DNC_2-Pad2)") (class "Default")
      (node (ref "IC1") (pin "2") (pinfunction "DNC_2_2") (pintype "bidirectional"))
    )
    (net (code "43") (name "unconnected-(IC1-DNC_3-Pad3)") (class "Default")
      (node (ref "IC1") (pin "3") (pinfunction "DNC_3_3") (pintype "bidirectional"))
    )
    (net (code "44") (name "unconnected-(IC1-DNC_4-Pad4)") (class "Default")
      (node (ref "IC1") (pin "4") (pinfunction "DNC_4_4") (pintype "bidirectional"))
    )
    (net (code "45") (name "unconnected-(IC1-DNC_5-Pad5)") (class "Default")
      (node (ref "IC1") (pin "5") (pinfunction "DNC_5_5") (pintype "bidirectional"))
    )
    (net (code "46") (name "unconnected-(IC1-DNC_6-Pad8)") (class "Default")
      (node (ref "IC1") (pin "8") (pinfunction "DNC_6_8") (pintype "bidirectional"))
    )
    (net (code "47") (name "unconnected-(IC1-DNC_7-Pad11)") (class "Default")
      (node (ref "IC1") (pin "11") (pinfunction "DNC_7_11") (pintype "bidirectional"))
    )
    (net (code "48") (name "unconnected-(IC1-DNC_8-Pad12)") (class "Default")
      (node (ref "IC1") (pin "12") (pinfunction "DNC_8_12") (pintype "bidirectional"))
    )
    (net (code "49") (name "unconnected-(IC1-DNC_9-Pad13)") (class "Default")
      (node (ref "IC1") (pin "13") (pinfunction "DNC_9_13") (pintype "bidirectional"))
    )
    (net (code "50") (name "unconnected-(IC1-DNC_10-Pad14)") (class "Default")
      (node (ref "IC1") (pin "14") (pinfunction "DNC_10_14") (pintype "bidirectional"))
    )
    (net (code "51") (name "unconnected-(IC1-DNC_11-Pad15)") (class "Default")
      (node (ref "IC1") (pin "15") (pinfunction "DNC_11_15") (pintype "bidirectional"))
    )
    (net (code "52") (name "unconnected-(IC1-DNC_12-Pad16)") (class "Default")
      (node (ref "IC1") (pin "16") (pinfunction "DNC_12_16") (pintype "bidirectional"))
    )
    (net (code "53") (name "unconnected-(IC1-DNC_13-Pad17)") (class "Default")
      (node (ref "IC1") (pin "17") (pinfunction "DNC_13_17") (pintype "bidirectional"))
    )
    (net (code "54") (name "unconnected-(IC1-DNC_14-Pad18)") (class "Default")
      (node (ref "IC1") (pin "18") (pinfunction "DNC_14_18") (pintype "bidirectional"))
    )
    (net (code "55") (name "unconnected-(LED11-DO-Pad1)") (class "Default")
      (node (ref "LED11") (pin "1") (pinfunction "DO_1") (pintype "output"))
    )
    (net (code "56") (name "unconnected-(U1-N{slash}A-Pad4)") (class "Default")
      (node (ref "U1") (pin "4") (pinfunction "N/A_4") (pintype "passive"))
    )
  )
)
